# Analog.net
KiCad netlist of a schematic drawn in Altium Designer
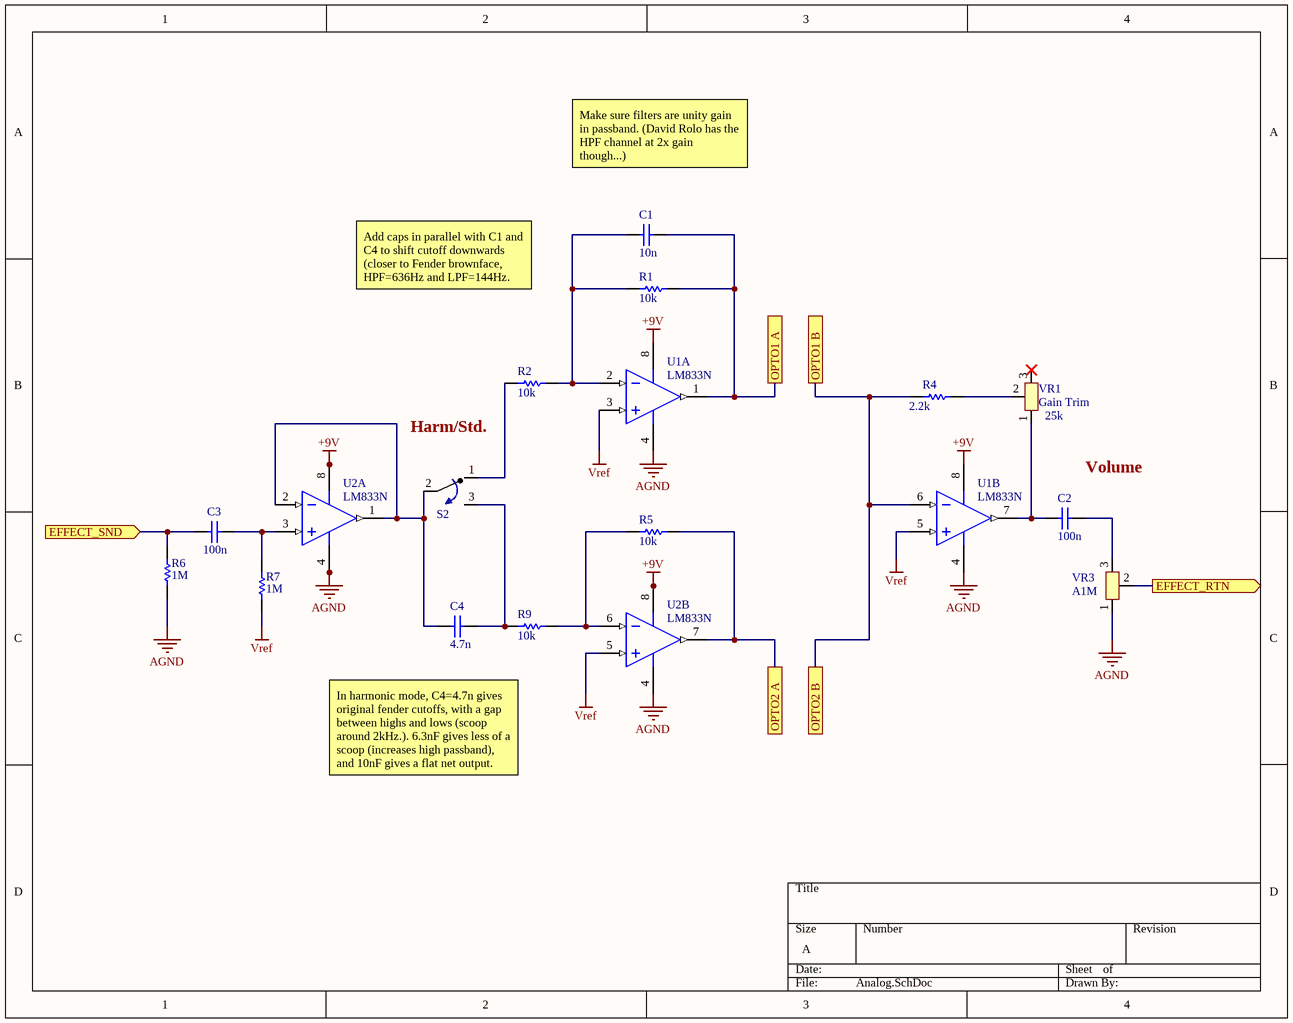
[diagram p0: Analog.SchDoc]

(export (version "E")
  (design (tool "Eeschema 10.0.6"))
  (components
    (comp (ref "C1")
      (value "10n")
      (footprint "RAD-0.3")
      (description "Capacitor")
      (fields (field (name "Comment") "Cap") (field (name "PUBLISHER") "Altium Limited"))
      (libsource (lib "Miscellaneous Devices") (part "Cap"))
    )
    (comp (ref "C2")
      (value "100n")
      (footprint "RAD-0.3")
      (description "Capacitor")
      (fields (field (name "Comment") "Cap") (field (name "PUBLISHER") "Altium Limited"))
      (libsource (lib "Miscellaneous Devices") (part "Cap"))
    )
    (comp (ref "C3")
      (value "100n")
      (footprint "RAD-0.3")
      (description "Capacitor")
      (fields (field (name "Comment") "Cap") (field (name "PUBLISHER") "Altium Limited"))
      (libsource (lib "Miscellaneous Devices") (part "Cap"))
    )
    (comp (ref "C4")
      (value "4.7n")
      (footprint "RAD-0.3")
      (description "Capacitor")
      (fields (field (name "Comment") "Cap") (field (name "PUBLISHER") "Altium Limited"))
      (libsource (lib "Miscellaneous Devices") (part "Cap"))
    )
    (comp (ref "R1")
      (value "10k")
      (footprint "AXIAL-0.3")
      (description "Resistor")
      (fields (field (name "Comment") "Res1") (field (name "PUBLISHER") "Altium Limited"))
      (libsource (lib "Miscellaneous Devices") (part "Res1"))
    )
    (comp (ref "R2")
      (value "10k")
      (footprint "AXIAL-0.3")
      (description "Resistor")
      (fields (field (name "Comment") "Res1") (field (name "PUBLISHER") "Altium Limited"))
      (libsource (lib "Miscellaneous Devices") (part "Res1"))
    )
    (comp (ref "R4")
      (value "2.2k")
      (footprint "AXIAL-0.3")
      (description "Resistor")
      (fields (field (name "Comment") "Res1") (field (name "PUBLISHER") "Altium Limited"))
      (libsource (lib "Miscellaneous Devices") (part "Res1"))
    )
    (comp (ref "R5")
      (value "10k")
      (footprint "AXIAL-0.3")
      (description "Resistor")
      (fields (field (name "Comment") "Res1") (field (name "PUBLISHER") "Altium Limited"))
      (libsource (lib "Miscellaneous Devices") (part "Res1"))
    )
    (comp (ref "R6")
      (value "1M")
      (footprint "AXIAL-0.3")
      (description "Resistor")
      (fields (field (name "Comment") "Res1") (field (name "PUBLISHER") "Altium Limited"))
      (libsource (lib "Miscellaneous Devices") (part "Res1"))
    )
    (comp (ref "R7")
      (value "1M")
      (footprint "AXIAL-0.3")
      (description "Resistor")
      (fields (field (name "Comment") "Res1") (field (name "PUBLISHER") "Altium Limited"))
      (libsource (lib "Miscellaneous Devices") (part "Res1"))
    )
    (comp (ref "R9")
      (value "10k")
      (footprint "AXIAL-0.3")
      (description "Resistor")
      (fields (field (name "Comment") "Res1") (field (name "PUBLISHER") "Altium Limited"))
      (libsource (lib "Miscellaneous Devices") (part "Res1"))
    )
    (comp (ref "S2")
      (value "SPDT Toggle")
      (footprint "SPDT Toggle")
      (libsource (lib "Parts") (part "SPDT Toggle"))
    )
    (comp (ref "U1")
      (value "LM833N")
      (footprint "626-05")
      (description "Low-Noise, Audio Dual Operational Amplifier")
      (fields (field (name "PUBLISHER") "Altium Limited"))
      (libsource (lib "ON Semi Operational Amplifier") (part "LM833N"))
    )
    (comp (ref "U2")
      (value "LM833N")
      (footprint "626-05")
      (description "Low-Noise, Audio Dual Operational Amplifier")
      (fields (field (name "PUBLISHER") "Altium Limited"))
      (libsource (lib "ON Semi Operational Amplifier") (part "LM833N"))
    )
    (comp (ref "VR1")
      (value "Gain Trim")
      (footprint "Trimpot - Bourns")
      (fields (field (name "ALTIUM_VALUE") "25k"))
      (libsource (lib "Parts") (part "Trimpot - Bourns"))
    )
    (comp (ref "VR3")
      (value "A1M")
      (footprint "Pot-16mm")
      (fields (field (name "Comment") "Pot-16mm"))
      (libsource (lib "Parts") (part "Pot-16mm"))
    )
  )
  (nets
    (net (code "1") (name "+9V") (class "Default")
      (node (ref "U1") (pin "8") (pinfunction "V+_8") (pintype "power_in"))
      (node (ref "U2") (pin "8") (pinfunction "V+_8") (pintype "power_in"))
    )
    (net (code "2") (name "/EFFECT_RTN") (class "Default")
      (node (ref "VR3") (pin "2") (pinfunction "2_2") (pintype "passive"))
    )
    (net (code "3") (name "/EFFECT_SND") (class "Default")
      (node (ref "C3") (pin "1") (pinfunction "1_1") (pintype "passive"))
      (node (ref "R6") (pin "2") (pinfunction "2_2") (pintype "passive"))
    )
    (net (code "4") (name "/OPTO1 A") (class "Default")
      (node (ref "C1") (pin "1") (pinfunction "1_1") (pintype "passive"))
      (node (ref "R1") (pin "1") (pinfunction "1_1") (pintype "passive"))
      (node (ref "U1") (pin "1") (pinfunction "OUT_1") (pintype "output"))
    )
    (net (code "5") (name "/OPTO1 B") (class "Default")
      (node (ref "R4") (pin "2") (pinfunction "2_2") (pintype "passive"))
      (node (ref "U1") (pin "6") (pinfunction "IN-_6") (pintype "input"))
    )
    (net (code "6") (name "/OPTO2 A") (class "Default")
      (node (ref "R5") (pin "1") (pinfunction "1_1") (pintype "passive"))
      (node (ref "U2") (pin "7") (pinfunction "OUT_7") (pintype "output"))
    )
    (net (code "7") (name "AGND") (class "Default")
      (node (ref "R6") (pin "1") (pinfunction "1_1") (pintype "passive"))
      (node (ref "U1") (pin "4") (pinfunction "V-_4") (pintype "power_in"))
      (node (ref "U2") (pin "4") (pinfunction "V-_4") (pintype "power_in"))
      (node (ref "VR3") (pin "1") (pinfunction "1_1") (pintype "passive"))
    )
    (net (code "8") (name "Net-(C2-Pad1)") (class "Default")
      (node (ref "C2") (pin "1") (pinfunction "1_1") (pintype "passive"))
      (node (ref "VR3") (pin "3") (pinfunction "3_3") (pintype "passive"))
    )
    (net (code "9") (name "Net-(C4-Pad1)") (class "Default")
      (node (ref "C4") (pin "1") (pinfunction "1_1") (pintype "passive"))
      (node (ref "R9") (pin "2") (pinfunction "2_2") (pintype "passive"))
      (node (ref "S2") (pin "3") (pinfunction "3_3") (pintype "passive"))
    )
    (net (code "10") (name "Net-(R2-Pad2)") (class "Default")
      (node (ref "R2") (pin "2") (pinfunction "2_2") (pintype "passive"))
      (node (ref "S2") (pin "1") (pinfunction "1_1") (pintype "passive"))
    )
    (net (code "11") (name "Net-(R4-Pad1)") (class "Default")
      (node (ref "R4") (pin "1") (pinfunction "1_1") (pintype "passive"))
      (node (ref "VR1") (pin "2") (pinfunction "2_2") (pintype "passive"))
    )
    (net (code "12") (name "Net-(U1A-IN-)") (class "Default")
      (node (ref "C1") (pin "2") (pinfunction "2_2") (pintype "passive"))
      (node (ref "R1") (pin "2") (pinfunction "2_2") (pintype "passive"))
      (node (ref "R2") (pin "1") (pinfunction "1_1") (pintype "passive"))
      (node (ref "U1") (pin "2") (pinfunction "IN-_2") (pintype "input"))
    )
    (net (code "13") (name "Net-(U1B-OUT)") (class "Default")
      (node (ref "C2") (pin "2") (pinfunction "2_2") (pintype "passive"))
      (node (ref "U1") (pin "7") (pinfunction "OUT_7") (pintype "output"))
      (node (ref "VR1") (pin "1") (pinfunction "1_1") (pintype "passive"))
    )
    (net (code "14") (name "Net-(U2A-IN+)") (class "Default")
      (node (ref "C3") (pin "2") (pinfunction "2_2") (pintype "passive"))
      (node (ref "R7") (pin "2") (pinfunction "2_2") (pintype "passive"))
      (node (ref "U2") (pin "3") (pinfunction "IN+_3") (pintype "input"))
    )
    (net (code "15") (name "Net-(U2A-IN-)") (class "Default")
      (node (ref "C4") (pin "2") (pinfunction "2_2") (pintype "passive"))
      (node (ref "S2") (pin "2") (pinfunction "2_2") (pintype "passive"))
      (node (ref "U2") (pin "1") (pinfunction "OUT_1") (pintype "output"))
      (node (ref "U2") (pin "2") (pinfunction "IN-_2") (pintype "input"))
    )
    (net (code "16") (name "Net-(U2B-IN-)") (class "Default")
      (node (ref "R5") (pin "2") (pinfunction "2_2") (pintype "passive"))
      (node (ref "R9") (pin "1") (pinfunction "1_1") (pintype "passive"))
      (node (ref "U2") (pin "6") (pinfunction "IN-_6") (pintype "input"))
    )
    (net (code "17") (name "Vref") (class "Default")
      (node (ref "R7") (pin "1") (pinfunction "1_1") (pintype "passive"))
      (node (ref "U1") (pin "3") (pinfunction "IN+_3") (pintype "input"))
      (node (ref "U1") (pin "5") (pinfunction "IN+_5") (pintype "input"))
      (node (ref "U2") (pin "5") (pinfunction "IN+_5") (pintype "input"))
    )
    (net (code "18") (name "unconnected-(VR1-Pad3)") (class "Default")
      (node (ref "VR1") (pin "3") (pinfunction "3_3") (pintype "passive+no_connect"))
    )
  )
)
